# board.net
KiCad netlist of a schematic drawn in EAGLE
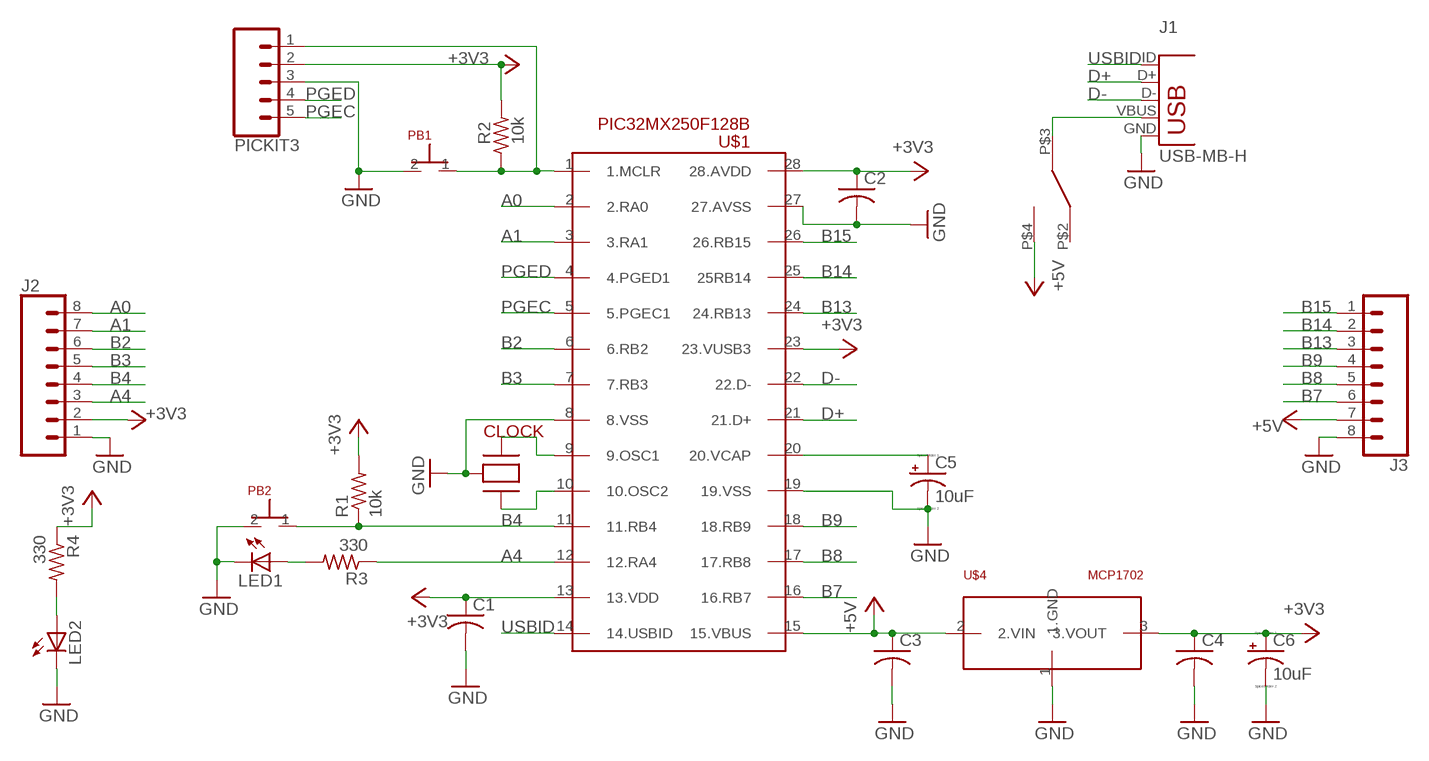
[diagram p0: schematic, sheet 1]

(export (version "E")
  (design (tool "Eeschema 10.0.6"))
  (components
    (comp (ref "C1")
      (value "C-US025-024X044")
      (footprint "eagle-import:C025-024X044")
      (libsource (lib "eagle-import") (part "C-US025-024X044"))
    )
    (comp (ref "C2")
      (value "C-US025-024X044")
      (footprint "eagle-import:C025-024X044")
      (libsource (lib "eagle-import") (part "C-US025-024X044"))
    )
    (comp (ref "C3")
      (value "C-US025-024X044")
      (footprint "eagle-import:C025-024X044")
      (libsource (lib "eagle-import") (part "C-US025-024X044"))
    )
    (comp (ref "C4")
      (value "C-US025-024X044")
      (footprint "eagle-import:C025-024X044")
      (libsource (lib "eagle-import") (part "C-US025-024X044"))
    )
    (comp (ref "C5")
      (value "10uF")
      (footprint "eagle-import:B45181A")
      (libsource (lib "eagle-import") (part "CPOL-USB45181A"))
    )
    (comp (ref "C6")
      (value "10uF")
      (footprint "eagle-import:B45181A")
      (libsource (lib "eagle-import") (part "CPOL-USB45181A"))
    )
    (comp (ref "CLOCK")
      (value "CLOCK")
      (footprint "eagle-import:CLOCK")
      (libsource (lib "eagle-import") (part "CLOCK"))
    )
    (comp (ref "J1")
      (value "USB-MB-H")
      (footprint "eagle-import:USB-MB-H")
      (libsource (lib "eagle-import") (part "USB-MB-H"))
    )
    (comp (ref "J2")
      (value "CONN_08\"")
      (footprint "eagle-import:1X08")
      (libsource (lib "eagle-import") (part "CONN_08{dblquote}"))
    )
    (comp (ref "J3")
      (value "CONN_08\"")
      (footprint "eagle-import:1X08")
      (libsource (lib "eagle-import") (part "CONN_08{dblquote}"))
    )
    (comp (ref "LED1")
      (value "LED3MM")
      (footprint "eagle-import:LED3MM")
      (libsource (lib "eagle-import") (part "LED3MM"))
    )
    (comp (ref "LED2")
      (value "LED3MM")
      (footprint "eagle-import:LED3MM")
      (libsource (lib "eagle-import") (part "LED3MM"))
    )
    (comp (ref "PB1")
      (value "PBUTTON")
      (footprint "eagle-import:PBUTTON")
      (libsource (lib "eagle-import") (part "PBUTTON"))
    )
    (comp (ref "PB2")
      (value "PBUTTON")
      (footprint "eagle-import:PBUTTON")
      (libsource (lib "eagle-import") (part "PBUTTON"))
    )
    (comp (ref "PICKIT3")
      (value "CONN_05")
      (footprint "eagle-import:1X05")
      (libsource (lib "eagle-import") (part "CONN_05"))
    )
    (comp (ref "R1")
      (value "10k")
      (footprint "eagle-import:0204_7")
      (libsource (lib "eagle-import") (part "R-US_0204/7"))
    )
    (comp (ref "R2")
      (value "10k")
      (footprint "eagle-import:0204_7")
      (libsource (lib "eagle-import") (part "R-US_0204/7"))
    )
    (comp (ref "R3")
      (value "330")
      (footprint "eagle-import:0204_7")
      (libsource (lib "eagle-import") (part "R-US_0204/7"))
    )
    (comp (ref "R4")
      (value "330")
      (footprint "eagle-import:0204_7")
      (libsource (lib "eagle-import") (part "R-US_0204/7"))
    )
    (comp (ref "U$1")
      (value "PIC32MX250F128B")
      (footprint "eagle-import:DIL28-3")
      (libsource (lib "eagle-import") (part "PIC32MX250F128B"))
    )
    (comp (ref "U$2")
      (value "SWITCH")
      (footprint "eagle-import:SWITCH")
      (libsource (lib "eagle-import") (part "SWITCH"))
    )
    (comp (ref "U$4")
      (value "MCP1702")
      (footprint "eagle-import:TO92")
      (libsource (lib "eagle-import") (part "MCP1702"))
    )
  )
  (nets
    (net (code "1") (name "+3V3") (class "Default")
      (node (ref "C1") (pin "1") (pinfunction "1_1") (pintype "passive"))
      (node (ref "C2") (pin "1") (pinfunction "1_1") (pintype "passive"))
      (node (ref "C4") (pin "1") (pinfunction "1_1") (pintype "passive"))
      (node (ref "C6") (pin "+") (pinfunction "+_+") (pintype "passive"))
      (node (ref "J2") (pin "2") (pinfunction "2_2") (pintype "passive"))
      (node (ref "PICKIT3") (pin "2") (pinfunction "2_2") (pintype "passive"))
      (node (ref "R1") (pin "2") (pinfunction "2_2") (pintype "passive"))
      (node (ref "R2") (pin "2") (pinfunction "2_2") (pintype "passive"))
      (node (ref "R4") (pin "1") (pinfunction "1_1") (pintype "passive"))
      (node (ref "U$1") (pin "13") (pinfunction "13.VDD_13") (pintype "bidirectional"))
      (node (ref "U$1") (pin "23") (pinfunction "23.VUSB3_23") (pintype "bidirectional"))
      (node (ref "U$1") (pin "28") (pinfunction "28.AVDD_28") (pintype "bidirectional"))
      (node (ref "U$4") (pin "3") (pinfunction "3.VOUT_3") (pintype "bidirectional"))
    )
    (net (code "2") (name "+5V") (class "Default")
      (node (ref "C3") (pin "1") (pinfunction "1_1") (pintype "passive"))
      (node (ref "J3") (pin "7") (pinfunction "7_7") (pintype "passive"))
      (node (ref "U$1") (pin "15") (pinfunction "15.VBUS_15") (pintype "bidirectional"))
      (node (ref "U$2") (pin "P$4") (pinfunction "4.OUT2_P$4") (pintype "bidirectional"))
      (node (ref "U$4") (pin "2") (pinfunction "2.VIN_2") (pintype "bidirectional"))
    )
    (net (code "3") (name "/A0") (class "Default")
      (node (ref "J2") (pin "8") (pinfunction "8_8") (pintype "passive"))
      (node (ref "U$1") (pin "2") (pinfunction "2.RA0_2") (pintype "bidirectional"))
    )
    (net (code "4") (name "/A1") (class "Default")
      (node (ref "J2") (pin "7") (pinfunction "7_7") (pintype "passive"))
      (node (ref "U$1") (pin "3") (pinfunction "3.RA1_3") (pintype "bidirectional"))
    )
    (net (code "5") (name "/A4") (class "Default")
      (node (ref "J2") (pin "3") (pinfunction "3_3") (pintype "passive"))
      (node (ref "R3") (pin "1") (pinfunction "1_1") (pintype "passive"))
      (node (ref "U$1") (pin "12") (pinfunction "12.RA4_12") (pintype "bidirectional"))
    )
    (net (code "6") (name "/B2") (class "Default")
      (node (ref "J2") (pin "6") (pinfunction "6_6") (pintype "passive"))
      (node (ref "U$1") (pin "6") (pinfunction "6.RB2_6") (pintype "bidirectional"))
    )
    (net (code "7") (name "/B3") (class "Default")
      (node (ref "J2") (pin "5") (pinfunction "5_5") (pintype "passive"))
      (node (ref "U$1") (pin "7") (pinfunction "7.RB3_7") (pintype "bidirectional"))
    )
    (net (code "8") (name "/B4") (class "Default")
      (node (ref "J2") (pin "4") (pinfunction "4_4") (pintype "passive"))
      (node (ref "PB2") (pin "1") (pinfunction "PIN1_1") (pintype "bidirectional"))
      (node (ref "R1") (pin "1") (pinfunction "1_1") (pintype "passive"))
      (node (ref "U$1") (pin "11") (pinfunction "11.RB4_11") (pintype "bidirectional"))
    )
    (net (code "9") (name "/B7") (class "Default")
      (node (ref "J3") (pin "6") (pinfunction "6_6") (pintype "passive"))
      (node (ref "U$1") (pin "16") (pinfunction "16.RB7_16") (pintype "bidirectional"))
    )
    (net (code "10") (name "/B8") (class "Default")
      (node (ref "J3") (pin "5") (pinfunction "5_5") (pintype "passive"))
      (node (ref "U$1") (pin "17") (pinfunction "17.RB8_17") (pintype "bidirectional"))
    )
    (net (code "11") (name "/B9") (class "Default")
      (node (ref "J3") (pin "4") (pinfunction "4_4") (pintype "passive"))
      (node (ref "U$1") (pin "18") (pinfunction "18.RB9_18") (pintype "bidirectional"))
    )
    (net (code "12") (name "/B13") (class "Default")
      (node (ref "J3") (pin "3") (pinfunction "3_3") (pintype "passive"))
      (node (ref "U$1") (pin "24") (pinfunction "24.RB13_24") (pintype "bidirectional"))
    )
    (net (code "13") (name "/B14") (class "Default")
      (node (ref "J3") (pin "2") (pinfunction "2_2") (pintype "passive"))
      (node (ref "U$1") (pin "25") (pinfunction "25RB14_25") (pintype "bidirectional"))
    )
    (net (code "14") (name "/B15") (class "Default")
      (node (ref "J3") (pin "1") (pinfunction "1_1") (pintype "passive"))
      (node (ref "U$1") (pin "26") (pinfunction "26.RB15_26") (pintype "bidirectional"))
    )
    (net (code "15") (name "/D+") (class "Default")
      (node (ref "J1") (pin "D+") (pinfunction "D+_D+") (pintype "bidirectional"))
      (node (ref "U$1") (pin "21") (pinfunction "21.D+_21") (pintype "bidirectional"))
    )
    (net (code "16") (name "/D-") (class "Default")
      (node (ref "J1") (pin "D-") (pinfunction "D-_D-") (pintype "bidirectional"))
      (node (ref "U$1") (pin "22") (pinfunction "22.D-_22") (pintype "bidirectional"))
    )
    (net (code "17") (name "/PGEC") (class "Default")
      (node (ref "PICKIT3") (pin "5") (pinfunction "5_5") (pintype "passive"))
      (node (ref "U$1") (pin "5") (pinfunction "5.PGEC1_5") (pintype "bidirectional"))
    )
    (net (code "18") (name "/PGED") (class "Default")
      (node (ref "PICKIT3") (pin "4") (pinfunction "4_4") (pintype "passive"))
      (node (ref "U$1") (pin "4") (pinfunction "4.PGED1_4") (pintype "bidirectional"))
    )
    (net (code "19") (name "/USBID") (class "Default")
      (node (ref "J1") (pin "ID") (pinfunction "ID_ID") (pintype "bidirectional"))
      (node (ref "U$1") (pin "14") (pinfunction "14.USBID_14") (pintype "bidirectional"))
    )
    (net (code "20") (name "GND") (class "Default")
      (node (ref "C1") (pin "2") (pinfunction "2_2") (pintype "passive"))
      (node (ref "C2") (pin "2") (pinfunction "2_2") (pintype "passive"))
      (node (ref "C3") (pin "2") (pinfunction "2_2") (pintype "passive"))
      (node (ref "C4") (pin "2") (pinfunction "2_2") (pintype "passive"))
      (node (ref "C5") (pin "-") (pinfunction "-_-") (pintype "passive"))
      (node (ref "C6") (pin "-") (pinfunction "-_-") (pintype "passive"))
      (node (ref "CLOCK") (pin "2") (pinfunction "2.GND_2") (pintype "bidirectional"))
      (node (ref "J1") (pin "GND") (pinfunction "GND_GND") (pintype "bidirectional"))
      (node (ref "J2") (pin "1") (pinfunction "1_1") (pintype "passive"))
      (node (ref "J3") (pin "8") (pinfunction "8_8") (pintype "passive"))
      (node (ref "LED1") (pin "K") (pinfunction "C_K") (pintype "passive"))
      (node (ref "LED2") (pin "K") (pinfunction "C_K") (pintype "passive"))
      (node (ref "PB1") (pin "2") (pinfunction "PIN2_2") (pintype "bidirectional"))
      (node (ref "PB2") (pin "2") (pinfunction "PIN2_2") (pintype "bidirectional"))
      (node (ref "PICKIT3") (pin "3") (pinfunction "3_3") (pintype "passive"))
      (node (ref "U$1") (pin "19") (pinfunction "19.VSS_19") (pintype "bidirectional"))
      (node (ref "U$1") (pin "27") (pinfunction "27.AVSS_27") (pintype "bidirectional"))
      (node (ref "U$1") (pin "8") (pinfunction "8.VSS_8") (pintype "bidirectional"))
      (node (ref "U$4") (pin "1") (pinfunction "1.GND_1") (pintype "bidirectional"))
    )
    (net (code "21") (name "Net-(CLOCK-1.OSC1)") (class "Default")
      (node (ref "CLOCK") (pin "1") (pinfunction "1.OSC1_1") (pintype "bidirectional"))
      (node (ref "U$1") (pin "9") (pinfunction "9.OSC1_9") (pintype "bidirectional"))
    )
    (net (code "22") (name "Net-(CLOCK-3.OSC2)") (class "Default")
      (node (ref "CLOCK") (pin "3") (pinfunction "3.OSC2_3") (pintype "bidirectional"))
      (node (ref "U$1") (pin "10") (pinfunction "10.OSC2_10") (pintype "bidirectional"))
    )
    (net (code "23") (name "Net-(LED1-PadA)") (class "Default")
      (node (ref "LED1") (pin "A") (pinfunction "A_A") (pintype "passive"))
      (node (ref "R3") (pin "2") (pinfunction "2_2") (pintype "passive"))
    )
    (net (code "24") (name "Net-(LED2-PadA)") (class "Default")
      (node (ref "LED2") (pin "A") (pinfunction "A_A") (pintype "passive"))
      (node (ref "R4") (pin "2") (pinfunction "2_2") (pintype "passive"))
    )
    (net (code "25") (name "Net-(PB1-PIN1)") (class "Default")
      (node (ref "PB1") (pin "1") (pinfunction "PIN1_1") (pintype "bidirectional"))
      (node (ref "PICKIT3") (pin "1") (pinfunction "1_1") (pintype "passive"))
      (node (ref "R2") (pin "1") (pinfunction "1_1") (pintype "passive"))
      (node (ref "U$1") (pin "1") (pinfunction "1.MCLR_1") (pintype "bidirectional"))
    )
    (net (code "26") (name "Net-(U$1-20.VCAP)") (class "Default")
      (node (ref "C5") (pin "+") (pinfunction "+_+") (pintype "passive"))
      (node (ref "U$1") (pin "20") (pinfunction "20.VCAP_20") (pintype "bidirectional"))
    )
    (net (code "27") (name "Net-(U$2-3.IN)") (class "Default")
      (node (ref "J1") (pin "VBUS") (pinfunction "VBUS_VBUS") (pintype "bidirectional"))
      (node (ref "U$2") (pin "P$3") (pinfunction "3.IN_P$3") (pintype "bidirectional"))
    )
    (net (code "28") (name "unconnected-(U$2-2.OUT1-PadP$2)") (class "Default")
      (node (ref "U$2") (pin "P$2") (pinfunction "2.OUT1_P$2") (pintype "bidirectional"))
    )
  )
)
